# stepper.net
KiCad netlist of a schematic drawn in Altium Designer
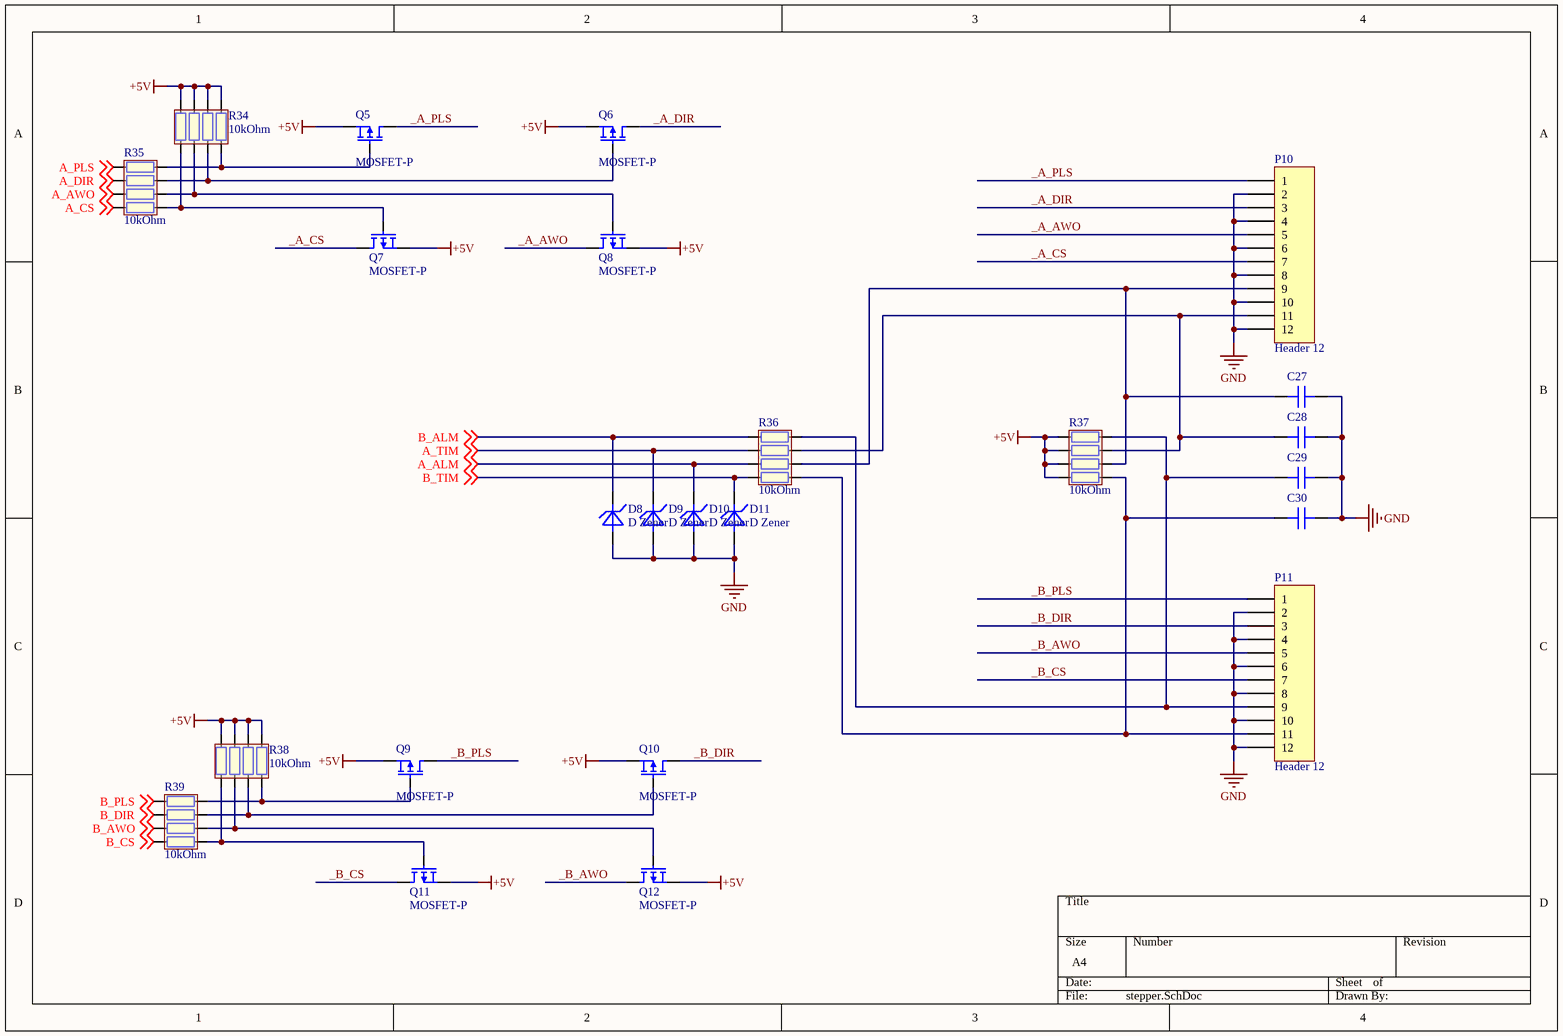
[diagram p0: stepper.SchDoc]

(export (version "E")
  (design (tool "Eeschema 10.0.6"))
  (components
    (comp (ref "C27")
      (value "100nF")
      (footprint "CAP 0805")
      (description "Non-polar capacitor")
      (fields (field (name "PUBLISHER") "Altium Limited"))
      (libsource (lib "MiLib") (part "Cap"))
    )
    (comp (ref "C28")
      (value "100nF")
      (footprint "CAP 0805")
      (description "Non-polar capacitor")
      (fields (field (name "PUBLISHER") "Altium Limited"))
      (libsource (lib "MiLib") (part "Cap"))
    )
    (comp (ref "C29")
      (value "100nF")
      (footprint "CAP 0805")
      (description "Non-polar capacitor")
      (fields (field (name "PUBLISHER") "Altium Limited"))
      (libsource (lib "MiLib") (part "Cap"))
    )
    (comp (ref "C30")
      (value "100nF")
      (footprint "CAP 0805")
      (description "Non-polar capacitor")
      (fields (field (name "PUBLISHER") "Altium Limited"))
      (libsource (lib "MiLib") (part "Cap"))
    )
    (comp (ref "D8")
      (value "D Zener")
      (footprint "CD3216-1206")
      (description "Zener Diode")
      (fields (field (name "PUBLISHER") "Altium Limited"))
      (libsource (lib "MiLib") (part "DZ"))
    )
    (comp (ref "D9")
      (value "D Zener")
      (footprint "CD3216-1206")
      (description "Zener Diode")
      (fields (field (name "PUBLISHER") "Altium Limited"))
      (libsource (lib "MiLib") (part "DZ"))
    )
    (comp (ref "D10")
      (value "D Zener")
      (footprint "CD3216-1206")
      (description "Zener Diode")
      (fields (field (name "PUBLISHER") "Altium Limited"))
      (libsource (lib "MiLib") (part "DZ"))
    )
    (comp (ref "D11")
      (value "D Zener")
      (footprint "CD3216-1206")
      (description "Zener Diode")
      (fields (field (name "PUBLISHER") "Altium Limited"))
      (libsource (lib "MiLib") (part "DZ"))
    )
    (comp (ref "P10")
      (value "Header 12")
      (footprint "MOLEX 53426-1210")
      (description "Header, 12-Pin")
      (fields (field (name "PUBLISHER") "Altium Limited"))
      (libsource (lib "MiLib") (part "Header 12"))
    )
    (comp (ref "P11")
      (value "Header 12")
      (footprint "MOLEX 53426-1210")
      (description "Header, 12-Pin")
      (fields (field (name "PUBLISHER") "Altium Limited"))
      (libsource (lib "MiLib") (part "Header 12"))
    )
    (comp (ref "Q5")
      (value "MOSFET-P")
      (footprint "SOT23-3")
      (description "P-Channel MOSFET")
      (fields (field (name "PUBLISHER") "Altium Limited"))
      (libsource (lib "MiLib") (part "MOSFET-P"))
    )
    (comp (ref "Q6")
      (value "MOSFET-P")
      (footprint "SOT23-3")
      (description "P-Channel MOSFET")
      (fields (field (name "PUBLISHER") "Altium Limited"))
      (libsource (lib "MiLib") (part "MOSFET-P"))
    )
    (comp (ref "Q7")
      (value "MOSFET-P")
      (footprint "SOT23-3")
      (description "P-Channel MOSFET")
      (fields (field (name "PUBLISHER") "Altium Limited"))
      (libsource (lib "MiLib") (part "MOSFET-P"))
    )
    (comp (ref "Q8")
      (value "MOSFET-P")
      (footprint "SOT23-3")
      (description "P-Channel MOSFET")
      (fields (field (name "PUBLISHER") "Altium Limited"))
      (libsource (lib "MiLib") (part "MOSFET-P"))
    )
    (comp (ref "Q9")
      (value "MOSFET-P")
      (footprint "SOT23-3")
      (description "P-Channel MOSFET")
      (fields (field (name "PUBLISHER") "Altium Limited"))
      (libsource (lib "MiLib") (part "MOSFET-P"))
    )
    (comp (ref "Q10")
      (value "MOSFET-P")
      (footprint "SOT23-3")
      (description "P-Channel MOSFET")
      (fields (field (name "PUBLISHER") "Altium Limited"))
      (libsource (lib "MiLib") (part "MOSFET-P"))
    )
    (comp (ref "Q11")
      (value "MOSFET-P")
      (footprint "SOT23-3")
      (description "P-Channel MOSFET")
      (fields (field (name "PUBLISHER") "Altium Limited"))
      (libsource (lib "MiLib") (part "MOSFET-P"))
    )
    (comp (ref "Q12")
      (value "MOSFET-P")
      (footprint "SOT23-3")
      (description "P-Channel MOSFET")
      (fields (field (name "PUBLISHER") "Altium Limited"))
      (libsource (lib "MiLib") (part "MOSFET-P"))
    )
    (comp (ref "R34") (value "10kOhm") (footprint "RES 0603 4PACK") (libsource (lib "") (part "Res 4Pack_1")))
    (comp (ref "R35") (value "10kOhm") (footprint "RES 0603 4PACK") (libsource (lib "") (part "Res 4Pack_2")))
    (comp (ref "R36") (value "10kOhm") (footprint "RES 0603 4PACK") (libsource (lib "") (part "Res 4Pack_2")))
    (comp (ref "R37")
      (value "10kOhm")
      (footprint "RES 0603 4PACK")
      (libsource (lib "MiLib") (part "Res 4Pack"))
    )
    (comp (ref "R38") (value "10kOhm") (footprint "RES 0603 4PACK") (libsource (lib "") (part "Res 4Pack_1")))
    (comp (ref "R39") (value "10kOhm") (footprint "RES 0603 4PACK") (libsource (lib "") (part "Res 4Pack_2")))
  )
  (nets
    (net (code "1") (name "+5V") (class "Default")
      (node (ref "Q10") (pin "2") (pinfunction "S_2") (pintype "passive"))
      (node (ref "Q11") (pin "2") (pinfunction "S_2") (pintype "passive"))
      (node (ref "Q12") (pin "2") (pinfunction "S_2") (pintype "passive"))
      (node (ref "Q5") (pin "2") (pinfunction "S_2") (pintype "passive"))
      (node (ref "Q6") (pin "2") (pinfunction "S_2") (pintype "passive"))
      (node (ref "Q7") (pin "2") (pinfunction "S_2") (pintype "passive"))
      (node (ref "Q8") (pin "2") (pinfunction "S_2") (pintype "passive"))
      (node (ref "Q9") (pin "2") (pinfunction "S_2") (pintype "passive"))
      (node (ref "R34") (pin "5") (pinfunction "5_5") (pintype "passive"))
      (node (ref "R34") (pin "6") (pinfunction "6_6") (pintype "passive"))
      (node (ref "R34") (pin "7") (pinfunction "7_7") (pintype "passive"))
      (node (ref "R34") (pin "8") (pinfunction "8_8") (pintype "passive"))
      (node (ref "R37") (pin "5") (pinfunction "5_5") (pintype "passive"))
      (node (ref "R37") (pin "6") (pinfunction "6_6") (pintype "passive"))
      (node (ref "R37") (pin "7") (pinfunction "7_7") (pintype "passive"))
      (node (ref "R37") (pin "8") (pinfunction "8_8") (pintype "passive"))
      (node (ref "R38") (pin "5") (pinfunction "5_5") (pintype "passive"))
      (node (ref "R38") (pin "6") (pinfunction "6_6") (pintype "passive"))
      (node (ref "R38") (pin "7") (pinfunction "7_7") (pintype "passive"))
      (node (ref "R38") (pin "8") (pinfunction "8_8") (pintype "passive"))
    )
    (net (code "2") (name "/_A_AWO") (class "Default")
      (node (ref "P10") (pin "5") (pinfunction "5_5") (pintype "passive"))
      (node (ref "Q8") (pin "3") (pinfunction "D_3") (pintype "passive"))
    )
    (net (code "3") (name "/_A_CS") (class "Default")
      (node (ref "P10") (pin "7") (pinfunction "7_7") (pintype "passive"))
      (node (ref "Q7") (pin "3") (pinfunction "D_3") (pintype "passive"))
    )
    (net (code "4") (name "/_A_DIR") (class "Default")
      (node (ref "P10") (pin "3") (pinfunction "3_3") (pintype "passive"))
      (node (ref "Q6") (pin "3") (pinfunction "D_3") (pintype "passive"))
    )
    (net (code "5") (name "/_A_PLS") (class "Default")
      (node (ref "P10") (pin "1") (pinfunction "1_1") (pintype "passive"))
      (node (ref "Q5") (pin "3") (pinfunction "D_3") (pintype "passive"))
    )
    (net (code "6") (name "/_B_AWO") (class "Default")
      (node (ref "P11") (pin "5") (pinfunction "5_5") (pintype "passive"))
      (node (ref "Q12") (pin "3") (pinfunction "D_3") (pintype "passive"))
    )
    (net (code "7") (name "/_B_CS") (class "Default")
      (node (ref "P11") (pin "7") (pinfunction "7_7") (pintype "passive"))
      (node (ref "Q11") (pin "3") (pinfunction "D_3") (pintype "passive"))
    )
    (net (code "8") (name "/_B_DIR") (class "Default")
      (node (ref "P11") (pin "3") (pinfunction "3_3") (pintype "passive"))
      (node (ref "Q10") (pin "3") (pinfunction "D_3") (pintype "passive"))
    )
    (net (code "9") (name "/_B_PLS") (class "Default")
      (node (ref "P11") (pin "1") (pinfunction "1_1") (pintype "passive"))
      (node (ref "Q9") (pin "3") (pinfunction "D_3") (pintype "passive"))
    )
    (net (code "10") (name "A_ALM") (class "Default")
      (node (ref "D10") (pin "2") (pinfunction "2_2") (pintype "passive"))
      (node (ref "R36") (pin "6") (pinfunction "6_6") (pintype "passive"))
    )
    (net (code "11") (name "A_AWO") (class "Default")
      (node (ref "R35") (pin "6") (pinfunction "6_6") (pintype "passive"))
    )
    (net (code "12") (name "A_CS") (class "Default")
      (node (ref "R35") (pin "5") (pinfunction "5_5") (pintype "passive"))
    )
    (net (code "13") (name "A_DIR") (class "Default")
      (node (ref "R35") (pin "7") (pinfunction "7_7") (pintype "passive"))
    )
    (net (code "14") (name "A_PLS") (class "Default")
      (node (ref "R35") (pin "8") (pinfunction "8_8") (pintype "passive"))
    )
    (net (code "15") (name "A_TIM") (class "Default")
      (node (ref "D9") (pin "2") (pinfunction "2_2") (pintype "passive"))
      (node (ref "R36") (pin "7") (pinfunction "7_7") (pintype "passive"))
    )
    (net (code "16") (name "B_ALM") (class "Default")
      (node (ref "D8") (pin "2") (pinfunction "2_2") (pintype "passive"))
      (node (ref "R36") (pin "8") (pinfunction "8_8") (pintype "passive"))
    )
    (net (code "17") (name "B_AWO") (class "Default")
      (node (ref "R39") (pin "6") (pinfunction "6_6") (pintype "passive"))
    )
    (net (code "18") (name "B_CS") (class "Default")
      (node (ref "R39") (pin "5") (pinfunction "5_5") (pintype "passive"))
    )
    (net (code "19") (name "B_DIR") (class "Default")
      (node (ref "R39") (pin "7") (pinfunction "7_7") (pintype "passive"))
    )
    (net (code "20") (name "B_PLS") (class "Default")
      (node (ref "R39") (pin "8") (pinfunction "8_8") (pintype "passive"))
    )
    (net (code "21") (name "B_TIM") (class "Default")
      (node (ref "D11") (pin "2") (pinfunction "2_2") (pintype "passive"))
      (node (ref "R36") (pin "5") (pinfunction "5_5") (pintype "passive"))
    )
    (net (code "22") (name "GND") (class "Default")
      (node (ref "C27") (pin "2") (pinfunction "2_2") (pintype "passive"))
      (node (ref "C28") (pin "2") (pinfunction "2_2") (pintype "passive"))
      (node (ref "C29") (pin "2") (pinfunction "2_2") (pintype "passive"))
      (node (ref "C30") (pin "2") (pinfunction "2_2") (pintype "passive"))
      (node (ref "D10") (pin "1") (pinfunction "1_1") (pintype "passive"))
      (node (ref "D11") (pin "1") (pinfunction "1_1") (pintype "passive"))
      (node (ref "D8") (pin "1") (pinfunction "1_1") (pintype "passive"))
      (node (ref "D9") (pin "1") (pinfunction "1_1") (pintype "passive"))
      (node (ref "P10") (pin "10") (pinfunction "10_10") (pintype "passive"))
      (node (ref "P10") (pin "12") (pinfunction "12_12") (pintype "passive"))
      (node (ref "P10") (pin "2") (pinfunction "2_2") (pintype "passive"))
      (node (ref "P10") (pin "4") (pinfunction "4_4") (pintype "passive"))
      (node (ref "P10") (pin "6") (pinfunction "6_6") (pintype "passive"))
      (node (ref "P10") (pin "8") (pinfunction "8_8") (pintype "passive"))
      (node (ref "P11") (pin "10") (pinfunction "10_10") (pintype "passive"))
      (node (ref "P11") (pin "12") (pinfunction "12_12") (pintype "passive"))
      (node (ref "P11") (pin "2") (pinfunction "2_2") (pintype "passive"))
      (node (ref "P11") (pin "4") (pinfunction "4_4") (pintype "passive"))
      (node (ref "P11") (pin "6") (pinfunction "6_6") (pintype "passive"))
      (node (ref "P11") (pin "8") (pinfunction "8_8") (pintype "passive"))
    )
    (net (code "23") (name "Net-(C27-Pad1)") (class "Default")
      (node (ref "C27") (pin "1") (pinfunction "1_1") (pintype "passive"))
      (node (ref "P10") (pin "9") (pinfunction "9_9") (pintype "passive"))
      (node (ref "R36") (pin "3") (pinfunction "3_3") (pintype "passive"))
      (node (ref "R37") (pin "2") (pinfunction "2_2") (pintype "passive"))
    )
    (net (code "24") (name "Net-(C28-Pad1)") (class "Default")
      (node (ref "C28") (pin "1") (pinfunction "1_1") (pintype "passive"))
      (node (ref "P10") (pin "11") (pinfunction "11_11") (pintype "passive"))
      (node (ref "R36") (pin "2") (pinfunction "2_2") (pintype "passive"))
      (node (ref "R37") (pin "3") (pinfunction "3_3") (pintype "passive"))
    )
    (net (code "25") (name "Net-(C29-Pad1)") (class "Default")
      (node (ref "C29") (pin "1") (pinfunction "1_1") (pintype "passive"))
      (node (ref "P11") (pin "9") (pinfunction "9_9") (pintype "passive"))
      (node (ref "R36") (pin "1") (pinfunction "1_1") (pintype "passive"))
      (node (ref "R37") (pin "4") (pinfunction "4_4") (pintype "passive"))
    )
    (net (code "26") (name "Net-(C30-Pad1)") (class "Default")
      (node (ref "C30") (pin "1") (pinfunction "1_1") (pintype "passive"))
      (node (ref "P11") (pin "11") (pinfunction "11_11") (pintype "passive"))
      (node (ref "R36") (pin "4") (pinfunction "4_4") (pintype "passive"))
      (node (ref "R37") (pin "1") (pinfunction "1_1") (pintype "passive"))
    )
    (net (code "27") (name "Net-(Q5-G)") (class "Default")
      (node (ref "Q5") (pin "1") (pinfunction "G_1") (pintype "passive"))
      (node (ref "R34") (pin "4") (pinfunction "4_4") (pintype "passive"))
      (node (ref "R35") (pin "1") (pinfunction "1_1") (pintype "passive"))
    )
    (net (code "28") (name "Net-(Q6-G)") (class "Default")
      (node (ref "Q6") (pin "1") (pinfunction "G_1") (pintype "passive"))
      (node (ref "R34") (pin "3") (pinfunction "3_3") (pintype "passive"))
      (node (ref "R35") (pin "2") (pinfunction "2_2") (pintype "passive"))
    )
    (net (code "29") (name "Net-(Q7-G)") (class "Default")
      (node (ref "Q7") (pin "1") (pinfunction "G_1") (pintype "passive"))
      (node (ref "R34") (pin "1") (pinfunction "1_1") (pintype "passive"))
      (node (ref "R35") (pin "4") (pinfunction "4_4") (pintype "passive"))
    )
    (net (code "30") (name "Net-(Q8-G)") (class "Default")
      (node (ref "Q8") (pin "1") (pinfunction "G_1") (pintype "passive"))
      (node (ref "R34") (pin "2") (pinfunction "2_2") (pintype "passive"))
      (node (ref "R35") (pin "3") (pinfunction "3_3") (pintype "passive"))
    )
    (net (code "31") (name "Net-(Q9-G)") (class "Default")
      (node (ref "Q9") (pin "1") (pinfunction "G_1") (pintype "passive"))
      (node (ref "R38") (pin "4") (pinfunction "4_4") (pintype "passive"))
      (node (ref "R39") (pin "1") (pinfunction "1_1") (pintype "passive"))
    )
    (net (code "32") (name "Net-(Q10-G)") (class "Default")
      (node (ref "Q10") (pin "1") (pinfunction "G_1") (pintype "passive"))
      (node (ref "R38") (pin "3") (pinfunction "3_3") (pintype "passive"))
      (node (ref "R39") (pin "2") (pinfunction "2_2") (pintype "passive"))
    )
    (net (code "33") (name "Net-(Q11-G)") (class "Default")
      (node (ref "Q11") (pin "1") (pinfunction "G_1") (pintype "passive"))
      (node (ref "R38") (pin "1") (pinfunction "1_1") (pintype "passive"))
      (node (ref "R39") (pin "4") (pinfunction "4_4") (pintype "passive"))
    )
    (net (code "34") (name "Net-(Q12-G)") (class "Default")
      (node (ref "Q12") (pin "1") (pinfunction "G_1") (pintype "passive"))
      (node (ref "R38") (pin "2") (pinfunction "2_2") (pintype "passive"))
      (node (ref "R39") (pin "3") (pinfunction "3_3") (pintype "passive"))
    )
  )
)
